# MB_RELAY.net
KiCad netlist of a schematic drawn in Altium Designer
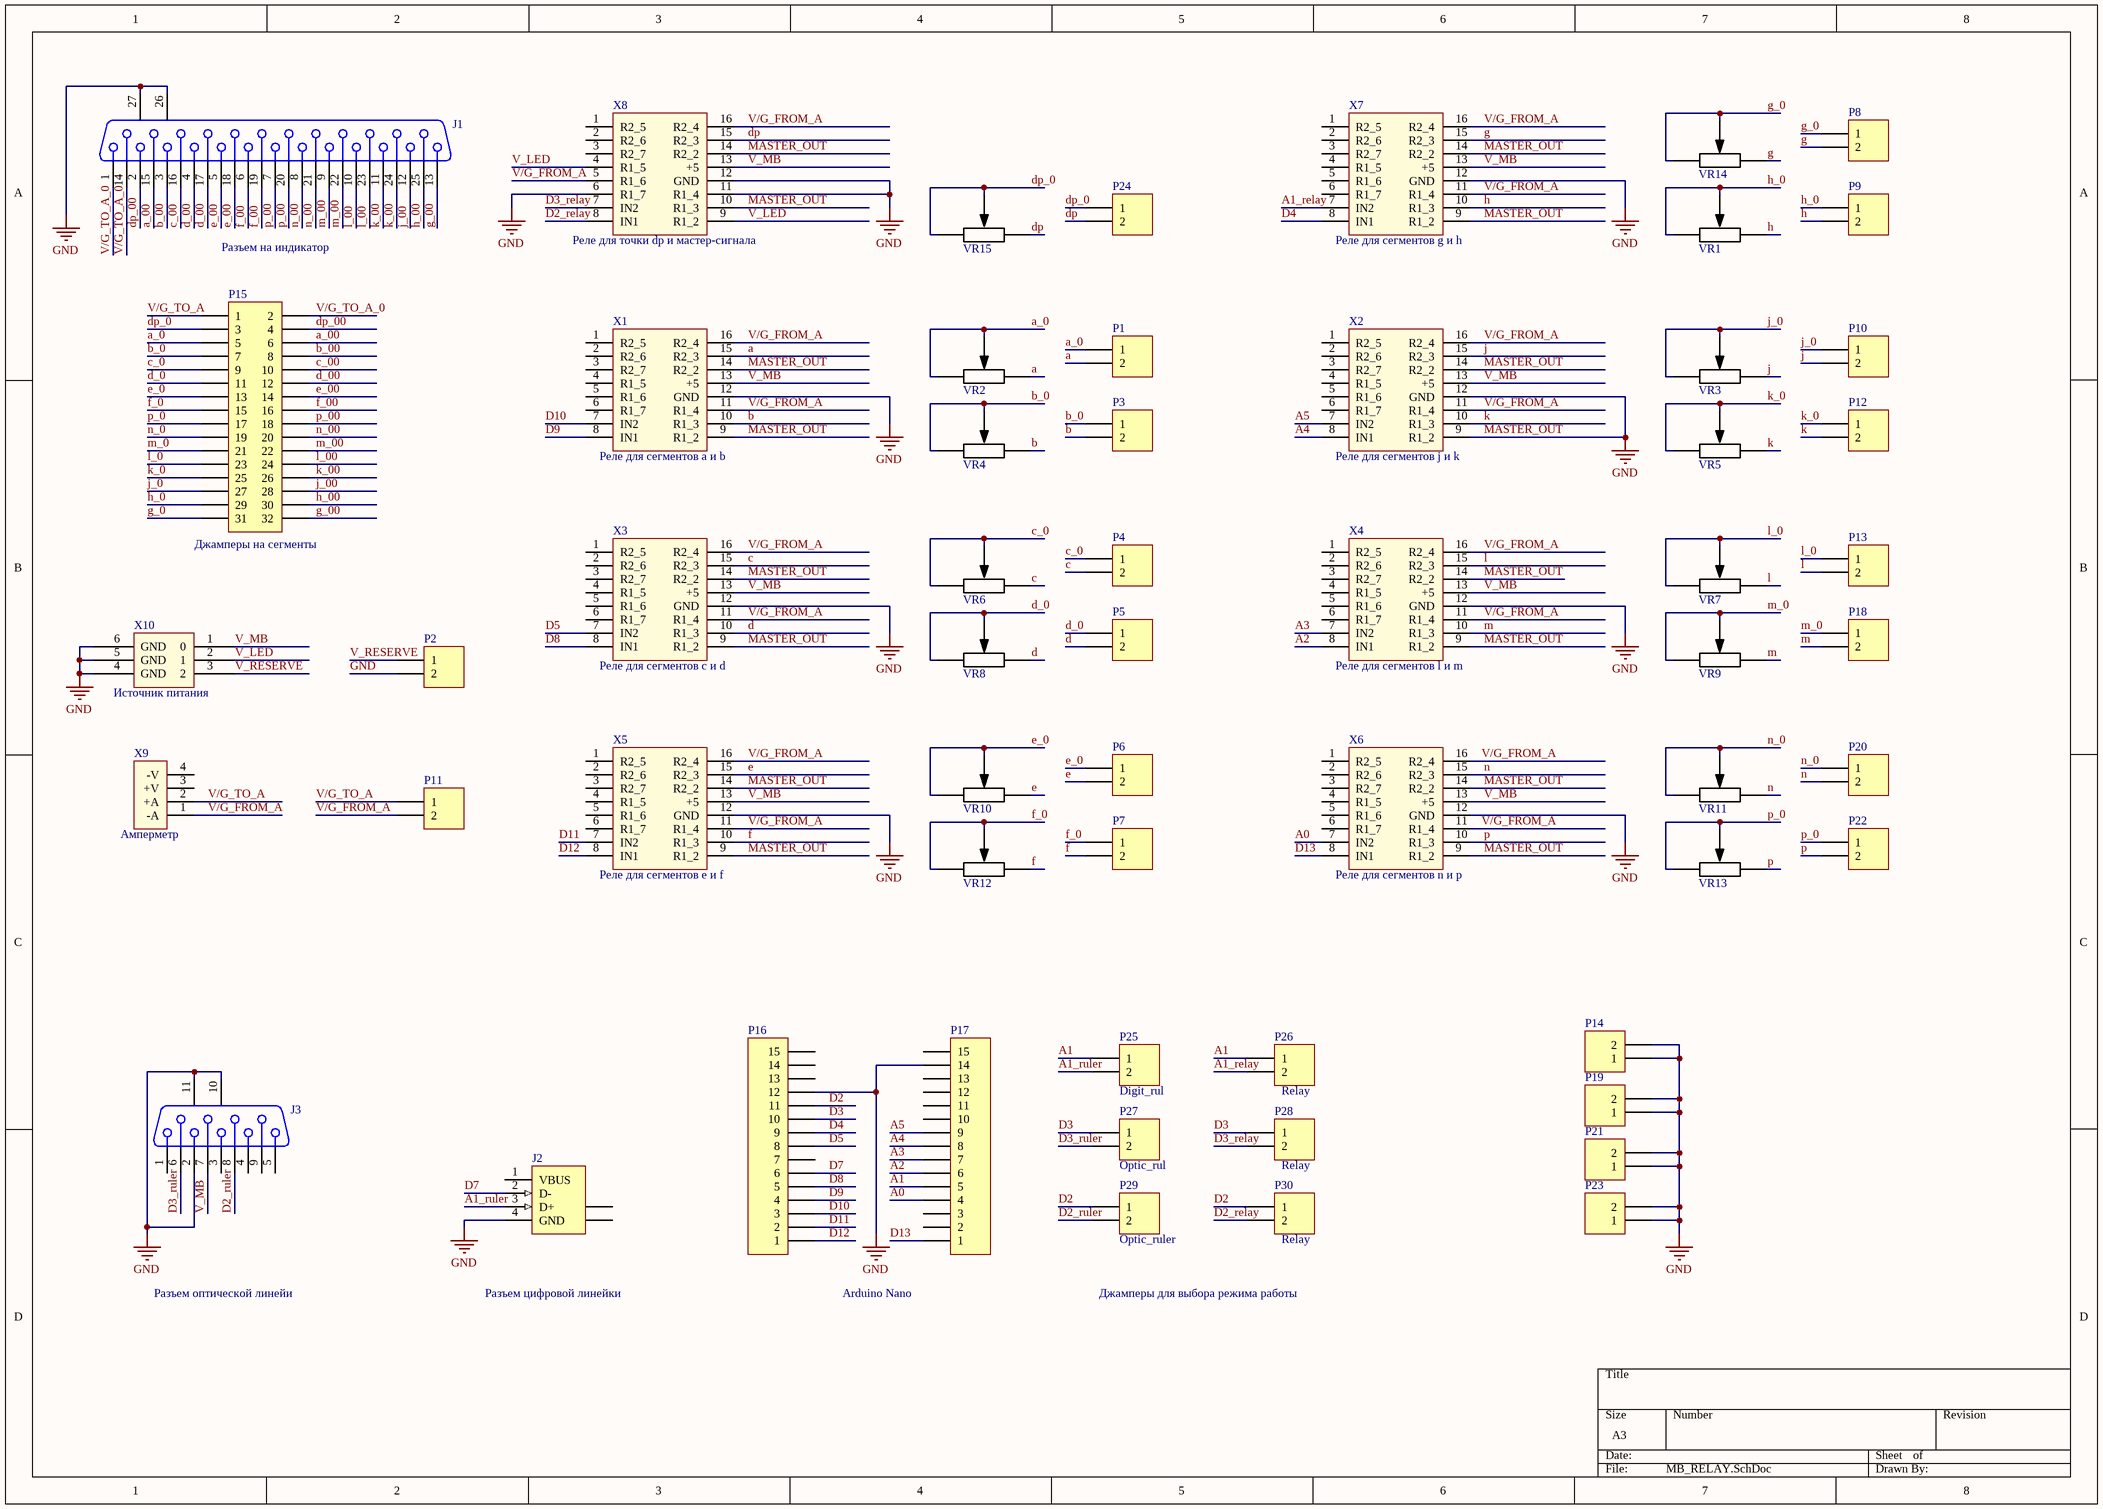
[diagram p0: MB_RELAY.SchDoc]

(export (version "E")
  (design (tool "Eeschema 10.0.6"))
  (components
    (comp (ref "J1")
      (value "D Connector 25")
      (footprint "DSUB1.385-2H25A")
      (description "Receptacle Assembly, 25 Position, Right Angle")
      (fields (field (name "PUBLISHER") "Altium Limited"))
      (libsource (lib "Miscellaneous Connectors") (part "D Connector 25"))
    )
    (comp (ref "J2")
      (value "1-353576-1")
      (footprint "353576")
      (description "USB 1.1, Right Angle, SMT, A Type, Receptacle, 4 Position, White")
      (fields (field (name "PUBLISHER") "Altium Limited"))
      (libsource (lib "AMP Serial Bus USB") (part "1-353576-1"))
    )
    (comp (ref "J3")
      (value "D Connector 9")
      (footprint "DSUB1.385-2H9")
      (description "Receptacle Assembly, 9 Position, Right Angle")
      (fields (field (name "PUBLISHER") "Altium Limited"))
      (libsource (lib "Miscellaneous Connectors") (part "D Connector 9"))
    )
    (comp (ref "P1")
      (value "Header 2")
      (footprint "HDR1X2")
      (description "Header, 2-Pin")
      (fields (field (name "PUBLISHER") "Altium Limited"))
      (libsource (lib "Miscellaneous Connectors") (part "Header 2"))
    )
    (comp (ref "P2")
      (value "Header 2")
      (footprint "HDR1X2")
      (description "Header, 2-Pin")
      (fields (field (name "PUBLISHER") "Altium Limited"))
      (libsource (lib "Miscellaneous Connectors") (part "Header 2"))
    )
    (comp (ref "P3")
      (value "Header 2")
      (footprint "HDR1X2")
      (description "Header, 2-Pin")
      (fields (field (name "PUBLISHER") "Altium Limited"))
      (libsource (lib "Miscellaneous Connectors") (part "Header 2"))
    )
    (comp (ref "P4")
      (value "Header 2")
      (footprint "HDR1X2")
      (description "Header, 2-Pin")
      (fields (field (name "PUBLISHER") "Altium Limited"))
      (libsource (lib "Miscellaneous Connectors") (part "Header 2"))
    )
    (comp (ref "P5")
      (value "Header 2")
      (footprint "HDR1X2")
      (description "Header, 2-Pin")
      (fields (field (name "PUBLISHER") "Altium Limited"))
      (libsource (lib "Miscellaneous Connectors") (part "Header 2"))
    )
    (comp (ref "P6")
      (value "GND")
      (footprint "HDR1X2")
      (description "Header, 2-Pin")
      (fields (field (name "PUBLISHER") "Altium Limited"))
      (libsource (lib "Miscellaneous Connectors") (part "Header 2"))
    )
    (comp (ref "P7")
      (value "GND")
      (footprint "HDR1X2")
      (description "Header, 2-Pin")
      (fields (field (name "PUBLISHER") "Altium Limited"))
      (libsource (lib "Miscellaneous Connectors") (part "Header 2"))
    )
    (comp (ref "P8")
      (value "GND")
      (footprint "HDR1X2")
      (description "Header, 2-Pin")
      (fields (field (name "PUBLISHER") "Altium Limited"))
      (libsource (lib "Miscellaneous Connectors") (part "Header 2"))
    )
    (comp (ref "P9")
      (value "GND")
      (footprint "HDR1X2")
      (description "Header, 2-Pin")
      (fields (field (name "PUBLISHER") "Altium Limited"))
      (libsource (lib "Miscellaneous Connectors") (part "Header 2"))
    )
    (comp (ref "P10")
      (value "Header 2")
      (footprint "HDR1X2")
      (description "Header, 2-Pin")
      (fields (field (name "PUBLISHER") "Altium Limited"))
      (libsource (lib "Miscellaneous Connectors") (part "Header 2"))
    )
    (comp (ref "P11")
      (value "Header 2")
      (footprint "HDR1X2")
      (description "Header, 2-Pin")
      (fields (field (name "PUBLISHER") "Altium Limited"))
      (libsource (lib "Miscellaneous Connectors") (part "Header 2"))
    )
    (comp (ref "P12")
      (value "Header 2")
      (footprint "HDR1X2")
      (description "Header, 2-Pin")
      (fields (field (name "PUBLISHER") "Altium Limited"))
      (libsource (lib "Miscellaneous Connectors") (part "Header 2"))
    )
    (comp (ref "P13")
      (value "GND")
      (footprint "HDR1X2")
      (description "Header, 2-Pin")
      (fields (field (name "PUBLISHER") "Altium Limited"))
      (libsource (lib "Miscellaneous Connectors") (part "Header 2"))
    )
    (comp (ref "P14")
      (value "GND")
      (footprint "HDR1X2")
      (description "Header, 2-Pin")
      (fields (field (name "PUBLISHER") "Altium Limited"))
      (libsource (lib "") (part "Header 2_1"))
    )
    (comp (ref "P15")
      (value "Header 16X2")
      (footprint "HDR2X16")
      (description "Header, 16-Pin, Dual row")
      (fields (field (name "PUBLISHER") "Altium Limited"))
      (libsource (lib "Miscellaneous Connectors") (part "Header 16X2"))
    )
    (comp (ref "P16")
      (value "Header 15")
      (footprint "HDR1X15")
      (description "Header, 15-Pin")
      (fields (field (name "PUBLISHER") "Altium Limited"))
      (libsource (lib "Miscellaneous Connectors") (part "Header 15"))
    )
    (comp (ref "P17")
      (value "Header 15")
      (footprint "HDR1X15")
      (description "Header, 15-Pin")
      (fields (field (name "PUBLISHER") "Altium Limited"))
      (libsource (lib "") (part "Header 15_1"))
    )
    (comp (ref "P18")
      (value "GND")
      (footprint "HDR1X2")
      (description "Header, 2-Pin")
      (fields (field (name "PUBLISHER") "Altium Limited"))
      (libsource (lib "Miscellaneous Connectors") (part "Header 2"))
    )
    (comp (ref "P19")
      (value "GND")
      (footprint "HDR1X2")
      (description "Header, 2-Pin")
      (fields (field (name "PUBLISHER") "Altium Limited"))
      (libsource (lib "") (part "Header 2_1"))
    )
    (comp (ref "P20")
      (value "GND")
      (footprint "HDR1X2")
      (description "Header, 2-Pin")
      (fields (field (name "PUBLISHER") "Altium Limited"))
      (libsource (lib "Miscellaneous Connectors") (part "Header 2"))
    )
    (comp (ref "P21")
      (value "GND")
      (footprint "HDR1X2")
      (description "Header, 2-Pin")
      (fields (field (name "PUBLISHER") "Altium Limited"))
      (libsource (lib "") (part "Header 2_1"))
    )
    (comp (ref "P22")
      (value "GND")
      (footprint "HDR1X2")
      (description "Header, 2-Pin")
      (fields (field (name "PUBLISHER") "Altium Limited"))
      (libsource (lib "Miscellaneous Connectors") (part "Header 2"))
    )
    (comp (ref "P23")
      (value "GND")
      (footprint "HDR1X2")
      (description "Header, 2-Pin")
      (fields (field (name "PUBLISHER") "Altium Limited"))
      (libsource (lib "") (part "Header 2_1"))
    )
    (comp (ref "P24")
      (value "GND")
      (footprint "HDR1X2")
      (description "Header, 2-Pin")
      (fields (field (name "PUBLISHER") "Altium Limited"))
      (libsource (lib "Miscellaneous Connectors") (part "Header 2"))
    )
    (comp (ref "P25")
      (value "Digit_rul")
      (footprint "HDR1X2")
      (description "Header, 2-Pin")
      (fields (field (name "PUBLISHER") "Altium Limited"))
      (libsource (lib "Miscellaneous Connectors") (part "Header 2"))
    )
    (comp (ref "P26")
      (value "Relay")
      (footprint "HDR1X2")
      (description "Header, 2-Pin")
      (fields (field (name "PUBLISHER") "Altium Limited"))
      (libsource (lib "Miscellaneous Connectors") (part "Header 2"))
    )
    (comp (ref "P27")
      (value "Optic_rul")
      (footprint "HDR1X2")
      (description "Header, 2-Pin")
      (fields (field (name "PUBLISHER") "Altium Limited"))
      (libsource (lib "Miscellaneous Connectors") (part "Header 2"))
    )
    (comp (ref "P28")
      (value "Relay")
      (footprint "HDR1X2")
      (description "Header, 2-Pin")
      (fields (field (name "PUBLISHER") "Altium Limited"))
      (libsource (lib "Miscellaneous Connectors") (part "Header 2"))
    )
    (comp (ref "P29")
      (value "Optic_ruler")
      (footprint "HDR1X2")
      (description "Header, 2-Pin")
      (fields (field (name "PUBLISHER") "Altium Limited"))
      (libsource (lib "Miscellaneous Connectors") (part "Header 2"))
    )
    (comp (ref "P30")
      (value "Relay")
      (footprint "HDR1X2")
      (description "Header, 2-Pin")
      (fields (field (name "PUBLISHER") "Altium Limited"))
      (libsource (lib "Miscellaneous Connectors") (part "Header 2"))
    )
    (comp (ref "VR1")
      (value "RES 3266W")
      (footprint "aab_Passive:RES 3266W")
      (libsource (lib "aab_Schlib") (part "RES 3266W"))
    )
    (comp (ref "VR2")
      (value "Переменнный резистор для")
      (footprint "aab_Passive:RES 3266W")
      (libsource (lib "aab_Schlib") (part "RES 3266W"))
    )
    (comp (ref "VR3")
      (value "RES 3266W")
      (footprint "aab_Passive:RES 3266W")
      (libsource (lib "aab_Schlib") (part "RES 3266W"))
    )
    (comp (ref "VR4")
      (value "RES 3266W")
      (footprint "aab_Passive:RES 3266W")
      (libsource (lib "aab_Schlib") (part "RES 3266W"))
    )
    (comp (ref "VR5")
      (value "RES 3266W")
      (footprint "aab_Passive:RES 3266W")
      (libsource (lib "aab_Schlib") (part "RES 3266W"))
    )
    (comp (ref "VR6")
      (value "RES 3266W")
      (footprint "aab_Passive:RES 3266W")
      (libsource (lib "aab_Schlib") (part "RES 3266W"))
    )
    (comp (ref "VR7")
      (value "RES 3266W")
      (footprint "aab_Passive:RES 3266W")
      (libsource (lib "aab_Schlib") (part "RES 3266W"))
    )
    (comp (ref "VR8")
      (value "RES 3266W")
      (footprint "aab_Passive:RES 3266W")
      (libsource (lib "aab_Schlib") (part "RES 3266W"))
    )
    (comp (ref "VR9")
      (value "RES 3266W")
      (footprint "aab_Passive:RES 3266W")
      (libsource (lib "aab_Schlib") (part "RES 3266W"))
    )
    (comp (ref "VR10")
      (value "RES 3266W")
      (footprint "aab_Passive:RES 3266W")
      (libsource (lib "aab_Schlib") (part "RES 3266W"))
    )
    (comp (ref "VR11")
      (value "RES 3266W")
      (footprint "aab_Passive:RES 3266W")
      (libsource (lib "aab_Schlib") (part "RES 3266W"))
    )
    (comp (ref "VR12")
      (value "RES 3266W")
      (footprint "aab_Passive:RES 3266W")
      (libsource (lib "aab_Schlib") (part "RES 3266W"))
    )
    (comp (ref "VR13")
      (value "RES 3266W")
      (footprint "aab_Passive:RES 3266W")
      (libsource (lib "aab_Schlib") (part "RES 3266W"))
    )
    (comp (ref "VR14")
      (value "RES 3266W")
      (footprint "aab_Passive:RES 3266W")
      (libsource (lib "aab_Schlib") (part "RES 3266W"))
    )
    (comp (ref "VR15")
      (value "RES 3266W")
      (footprint "aab_Passive:RES 3266W")
      (libsource (lib "aab_Schlib") (part "RES 3266W"))
    )
    (comp (ref "X1")
      (value "Реле для сегментов a и b")
      (footprint "MEZ_RELAY")
      (libsource (lib "msp_SchLib") (part "MEZ_RELAY"))
    )
    (comp (ref "X2")
      (value "Реле для сегментов j и k")
      (footprint "MEZ_RELAY")
      (libsource (lib "msp_SchLib") (part "MEZ_RELAY"))
    )
    (comp (ref "X3")
      (value "Реле для сегментов c и d")
      (footprint "MEZ_RELAY")
      (libsource (lib "msp_SchLib") (part "MEZ_RELAY"))
    )
    (comp (ref "X4")
      (value "Реле для сегментов l и m")
      (footprint "MEZ_RELAY")
      (libsource (lib "msp_SchLib") (part "MEZ_RELAY"))
    )
    (comp (ref "X5")
      (value "Реле для сегментов e и f")
      (footprint "MEZ_RELAY")
      (libsource (lib "msp_SchLib") (part "MEZ_RELAY"))
    )
    (comp (ref "X6")
      (value "Реле для сегментов n и p")
      (footprint "MEZ_RELAY")
      (libsource (lib "msp_SchLib") (part "MEZ_RELAY"))
    )
    (comp (ref "X7")
      (value "Реле для сегментов g и h")
      (footprint "MEZ_RELAY")
      (libsource (lib "msp_SchLib") (part "MEZ_RELAY"))
    )
    (comp (ref "X8")
      (value "Реле для точки dp и мастер-сигнала")
      (footprint "MEZ_RELAY")
      (libsource (lib "msp_SchLib") (part "MEZ_RELAY"))
    )
    (comp (ref "X9")
      (value "Амперметр")
      (footprint "vpl_Passive:AMP_VOLTMETER")
      (libsource (lib "msp_SchLib") (part "AMP_VOLTMETR"))
    )
    (comp (ref "X10")
      (value "Источник питания")
      (footprint "vpl_Passive:POWER")
      (libsource (lib "msp_SchLib") (part "POWER"))
    )
  )
  (nets
    (net (code "1") (name "/A0") (class "Default")
      (node (ref "P17") (pin "4") (pinfunction "4_4") (pintype "passive"))
      (node (ref "X6") (pin "7") (pinfunction "IN2_7") (pintype "passive"))
    )
    (net (code "2") (name "/A1") (class "Default")
      (node (ref "P17") (pin "5") (pinfunction "5_5") (pintype "passive"))
      (node (ref "P25") (pin "1") (pinfunction "1_1") (pintype "passive"))
      (node (ref "P26") (pin "1") (pinfunction "1_1") (pintype "passive"))
    )
    (net (code "3") (name "/A1_relay") (class "Default")
      (node (ref "P26") (pin "2") (pinfunction "2_2") (pintype "passive"))
      (node (ref "X7") (pin "7") (pinfunction "IN2_7") (pintype "passive"))
    )
    (net (code "4") (name "/A1_ruler") (class "Default")
      (node (ref "J2") (pin "3") (pinfunction "D+_3") (pintype "input"))
      (node (ref "P25") (pin "2") (pinfunction "2_2") (pintype "passive"))
    )
    (net (code "5") (name "/A2") (class "Default")
      (node (ref "P17") (pin "6") (pinfunction "6_6") (pintype "passive"))
      (node (ref "X4") (pin "8") (pinfunction "IN1_8") (pintype "passive"))
    )
    (net (code "6") (name "/A3") (class "Default")
      (node (ref "P17") (pin "7") (pinfunction "7_7") (pintype "passive"))
      (node (ref "X4") (pin "7") (pinfunction "IN2_7") (pintype "passive"))
    )
    (net (code "7") (name "/A4") (class "Default")
      (node (ref "P17") (pin "8") (pinfunction "8_8") (pintype "passive"))
      (node (ref "X2") (pin "8") (pinfunction "IN1_8") (pintype "passive"))
    )
    (net (code "8") (name "/A5") (class "Default")
      (node (ref "P17") (pin "9") (pinfunction "9_9") (pintype "passive"))
      (node (ref "X2") (pin "7") (pinfunction "IN2_7") (pintype "passive"))
    )
    (net (code "9") (name "/D2") (class "Default")
      (node (ref "P16") (pin "11") (pinfunction "11_11") (pintype "passive"))
      (node (ref "P29") (pin "1") (pinfunction "1_1") (pintype "passive"))
      (node (ref "P30") (pin "1") (pinfunction "1_1") (pintype "passive"))
    )
    (net (code "10") (name "/D2_relay") (class "Default")
      (node (ref "P30") (pin "2") (pinfunction "2_2") (pintype "passive"))
      (node (ref "X8") (pin "8") (pinfunction "IN1_8") (pintype "passive"))
    )
    (net (code "11") (name "/D2_ruler") (class "Default")
      (node (ref "J3") (pin "8") (pinfunction "8_8") (pintype "passive"))
      (node (ref "P29") (pin "2") (pinfunction "2_2") (pintype "passive"))
    )
    (net (code "12") (name "/D3") (class "Default")
      (node (ref "P16") (pin "10") (pinfunction "10_10") (pintype "passive"))
      (node (ref "P27") (pin "1") (pinfunction "1_1") (pintype "passive"))
      (node (ref "P28") (pin "1") (pinfunction "1_1") (pintype "passive"))
    )
    (net (code "13") (name "/D3_relay") (class "Default")
      (node (ref "P28") (pin "2") (pinfunction "2_2") (pintype "passive"))
      (node (ref "X8") (pin "7") (pinfunction "IN2_7") (pintype "passive"))
    )
    (net (code "14") (name "/D3_ruler") (class "Default")
      (node (ref "J3") (pin "6") (pinfunction "6_6") (pintype "passive"))
      (node (ref "P27") (pin "2") (pinfunction "2_2") (pintype "passive"))
    )
    (net (code "15") (name "/D4") (class "Default")
      (node (ref "P16") (pin "9") (pinfunction "9_9") (pintype "passive"))
      (node (ref "X7") (pin "8") (pinfunction "IN1_8") (pintype "passive"))
    )
    (net (code "16") (name "/D5") (class "Default")
      (node (ref "P16") (pin "8") (pinfunction "8_8") (pintype "passive"))
      (node (ref "X3") (pin "7") (pinfunction "IN2_7") (pintype "passive"))
    )
    (net (code "17") (name "/D7") (class "Default")
      (node (ref "J2") (pin "2") (pinfunction "D-_2") (pintype "input"))
      (node (ref "P16") (pin "6") (pinfunction "6_6") (pintype "passive"))
    )
    (net (code "18") (name "/D8") (class "Default")
      (node (ref "P16") (pin "5") (pinfunction "5_5") (pintype "passive"))
      (node (ref "X3") (pin "8") (pinfunction "IN1_8") (pintype "passive"))
    )
    (net (code "19") (name "/D9") (class "Default")
      (node (ref "P16") (pin "4") (pinfunction "4_4") (pintype "passive"))
      (node (ref "X1") (pin "8") (pinfunction "IN1_8") (pintype "passive"))
    )
    (net (code "20") (name "/D10") (class "Default")
      (node (ref "P16") (pin "3") (pinfunction "3_3") (pintype "passive"))
      (node (ref "X1") (pin "7") (pinfunction "IN2_7") (pintype "passive"))
    )
    (net (code "21") (name "/D11") (class "Default")
      (node (ref "P16") (pin "2") (pinfunction "2_2") (pintype "passive"))
      (node (ref "X5") (pin "7") (pinfunction "IN2_7") (pintype "passive"))
    )
    (net (code "22") (name "/D12") (class "Default")
      (node (ref "P16") (pin "1") (pinfunction "1_1") (pintype "passive"))
      (node (ref "X5") (pin "8") (pinfunction "IN1_8") (pintype "passive"))
    )
    (net (code "23") (name "/D13") (class "Default")
      (node (ref "P17") (pin "1") (pinfunction "1_1") (pintype "passive"))
      (node (ref "X6") (pin "8") (pinfunction "IN1_8") (pintype "passive"))
    )
    (net (code "24") (name "/V_LED") (class "Default")
      (node (ref "X10") (pin "2") (pinfunction "1_2") (pintype "passive"))
      (node (ref "X8") (pin "4") (pinfunction "R1_5_4") (pintype "passive"))
      (node (ref "X8") (pin "9") (pinfunction "R1_2_9") (pintype "passive"))
    )
    (net (code "25") (name "/V_MB") (class "Default")
      (node (ref "J3") (pin "7") (pinfunction "7_7") (pintype "passive"))
      (node (ref "X1") (pin "13") (pinfunction "+5_13") (pintype "passive"))
      (node (ref "X10") (pin "1") (pinfunction "0_1") (pintype "passive"))
      (node (ref "X2") (pin "13") (pinfunction "+5_13") (pintype "passive"))
      (node (ref "X3") (pin "13") (pinfunction "+5_13") (pintype "passive"))
      (node (ref "X4") (pin "13") (pinfunction "+5_13") (pintype "passive"))
      (node (ref "X5") (pin "13") (pinfunction "+5_13") (pintype "passive"))
      (node (ref "X6") (pin "13") (pinfunction "+5_13") (pintype "passive"))
      (node (ref "X7") (pin "13") (pinfunction "+5_13") (pintype "passive"))
      (node (ref "X8") (pin "13") (pinfunction "+5_13") (pintype "passive"))
    )
    (net (code "26") (name "/V_RESERVE") (class "Default")
      (node (ref "P2") (pin "1") (pinfunction "1_1") (pintype "passive"))
      (node (ref "X10") (pin "3") (pinfunction "2_3") (pintype "passive"))
    )
    (net (code "27") (name "/V{slash}G_FROM_A") (class "Default")
      (node (ref "P11") (pin "2") (pinfunction "2_2") (pintype "passive"))
      (node (ref "X1") (pin "11") (pinfunction "R1_4_11") (pintype "passive"))
      (node (ref "X1") (pin "16") (pinfunction "R2_4_16") (pintype "passive"))
      (node (ref "X2") (pin "11") (pinfunction "R1_4_11") (pintype "passive"))
      (node (ref "X2") (pin "16") (pinfunction "R2_4_16") (pintype "passive"))
      (node (ref "X3") (pin "11") (pinfunction "R1_4_11") (pintype "passive"))
      (node (ref "X3") (pin "16") (pinfunction "R2_4_16") (pintype "passive"))
      (node (ref "X4") (pin "11") (pinfunction "R1_4_11") (pintype "passive"))
      (node (ref "X4") (pin "16") (pinfunction "R2_4_16") (pintype "passive"))
      (node (ref "X5") (pin "11") (pinfunction "R1_4_11") (pintype "passive"))
      (node (ref "X5") (pin "16") (pinfunction "R2_4_16") (pintype "passive"))
      (node (ref "X6") (pin "11") (pinfunction "R1_4_11") (pintype "passive"))
      (node (ref "X6") (pin "16") (pinfunction "R2_4_16") (pintype "passive"))
      (node (ref "X7") (pin "11") (pinfunction "R1_4_11") (pintype "passive"))
      (node (ref "X7") (pin "16") (pinfunction "R2_4_16") (pintype "passive"))
      (node (ref "X8") (pin "16") (pinfunction "R2_4_16") (pintype "passive"))
      (node (ref "X8") (pin "5") (pinfunction "R1_6_5") (pintype "passive"))
      (node (ref "X9") (pin "1") (pinfunction "-A_1") (pintype "passive"))
    )
    (net (code "28") (name "/V{slash}G_TO_A") (class "Default")
      (node (ref "P11") (pin "1") (pinfunction "1_1") (pintype "passive"))
      (node (ref "P15") (pin "1") (pinfunction "1_1") (pintype "passive"))
      (node (ref "X9") (pin "2") (pinfunction "+A_2") (pintype "passive"))
    )
    (net (code "29") (name "/V{slash}G_TO_A_0") (class "Default")
      (node (ref "J1") (pin "1") (pinfunction "1_1") (pintype "passive"))
      (node (ref "J1") (pin "14") (pinfunction "14_14") (pintype "passive"))
      (node (ref "P15") (pin "2") (pinfunction "2_2") (pintype "passive"))
    )
    (net (code "30") (name "/a") (class "Default")
      (node (ref "P1") (pin "2") (pinfunction "2_2") (pintype "passive"))
      (node (ref "VR2") (pin "3") (pinfunction "3_3") (pintype "passive"))
      (node (ref "X1") (pin "15") (pinfunction "R2_3_15") (pintype "passive"))
    )
    (net (code "31") (name "/a_0") (class "Default")
      (node (ref "P1") (pin "1") (pinfunction "1_1") (pintype "passive"))
      (node (ref "P15") (pin "5") (pinfunction "5_5") (pintype "passive"))
      (node (ref "VR2") (pin "1") (pinfunction "1_1") (pintype "passive"))
      (node (ref "VR2") (pin "2") (pinfunction "2_2") (pintype "passive"))
    )
    (net (code "32") (name "/a_00") (class "Default")
      (node (ref "J1") (pin "15") (pinfunction "15_15") (pintype "passive"))
      (node (ref "P15") (pin "6") (pinfunction "6_6") (pintype "passive"))
    )
    (net (code "33") (name "/b") (class "Default")
      (node (ref "P3") (pin "2") (pinfunction "2_2") (pintype "passive"))
      (node (ref "VR4") (pin "3") (pinfunction "3_3") (pintype "passive"))
      (node (ref "X1") (pin "10") (pinfunction "R1_3_10") (pintype "passive"))
    )
    (net (code "34") (name "/b_00") (class "Default")
      (node (ref "J1") (pin "3") (pinfunction "3_3") (pintype "passive"))
      (node (ref "P15") (pin "8") (pinfunction "8_8") (pintype "passive"))
    )
    (net (code "35") (name "/b_0") (class "Default")
      (node (ref "P15") (pin "7") (pinfunction "7_7") (pintype "passive"))
      (node (ref "P3") (pin "1") (pinfunction "1_1") (pintype "passive"))
      (node (ref "VR4") (pin "1") (pinfunction "1_1") (pintype "passive"))
      (node (ref "VR4") (pin "2") (pinfunction "2_2") (pintype "passive"))
    )
    (net (code "36") (name "/c") (class "Default")
      (node (ref "P4") (pin "2") (pinfunction "2_2") (pintype "passive"))
      (node (ref "VR6") (pin "3") (pinfunction "3_3") (pintype "passive"))
      (node (ref "X3") (pin "15") (pinfunction "R2_3_15") (pintype "passive"))
    )
    (net (code "37") (name "/c_0") (class "Default")
      (node (ref "P15") (pin "9") (pinfunction "9_9") (pintype "passive"))
      (node (ref "P4") (pin "1") (pinfunction "1_1") (pintype "passive"))
      (node (ref "VR6") (pin "1") (pinfunction "1_1") (pintype "passive"))
      (node (ref "VR6") (pin "2") (pinfunction "2_2") (pintype "passive"))
    )
    (net (code "38") (name "/c_00") (class "Default")
      (node (ref "J1") (pin "16") (pinfunction "16_16") (pintype "passive"))
      (node (ref "P15") (pin "10") (pinfunction "10_10") (pintype "passive"))
    )
    (net (code "39") (name "/d") (class "Default")
      (node (ref "P5") (pin "2") (pinfunction "2_2") (pintype "passive"))
      (node (ref "VR8") (pin "3") (pinfunction "3_3") (pintype "passive"))
      (node (ref "X3") (pin "10") (pinfunction "R1_3_10") (pintype "passive"))
    )
    (net (code "40") (name "/d_0") (class "Default")
      (node (ref "P15") (pin "11") (pinfunction "11_11") (pintype "passive"))
      (node (ref "P5") (pin "1") (pinfunction "1_1") (pintype "passive"))
      (node (ref "VR8") (pin "1") (pinfunction "1_1") (pintype "passive"))
      (node (ref "VR8") (pin "2") (pinfunction "2_2") (pintype "passive"))
    )
    (net (code "41") (name "/d_00") (class "Default")
      (node (ref "J1") (pin "17") (pinfunction "17_17") (pintype "passive"))
      (node (ref "J1") (pin "4") (pinfunction "4_4") (pintype "passive"))
      (node (ref "P15") (pin "12") (pinfunction "12_12") (pintype "passive"))
    )
    (net (code "42") (name "/dp") (class "Default")
      (node (ref "P24") (pin "2") (pinfunction "2_2") (pintype "passive"))
      (node (ref "VR15") (pin "3") (pinfunction "3_3") (pintype "passive"))
      (node (ref "X8") (pin "15") (pinfunction "R2_3_15") (pintype "passive"))
    )
    (net (code "43") (name "/dp_0") (class "Default")
      (node (ref "P15") (pin "3") (pinfunction "3_3") (pintype "passive"))
      (node (ref "P24") (pin "1") (pinfunction "1_1") (pintype "passive"))
      (node (ref "VR15") (pin "1") (pinfunction "1_1") (pintype "passive"))
      (node (ref "VR15") (pin "2") (pinfunction "2_2") (pintype "passive"))
    )
    (net (code "44") (name "/dp_00") (class "Default")
      (node (ref "J1") (pin "2") (pinfunction "2_2") (pintype "passive"))
      (node (ref "P15") (pin "4") (pinfunction "4_4") (pintype "passive"))
    )
    (net (code "45") (name "/e") (class "Default")
      (node (ref "P6") (pin "2") (pinfunction "2_2") (pintype "passive"))
      (node (ref "VR10") (pin "3") (pinfunction "3_3") (pintype "passive"))
      (node (ref "X5") (pin "15") (pinfunction "R2_3_15") (pintype "passive"))
    )
    (net (code "46") (name "/e_0") (class "Default")
      (node (ref "P15") (pin "13") (pinfunction "13_13") (pintype "passive"))
      (node (ref "P6") (pin "1") (pinfunction "1_1") (pintype "passive"))
      (node (ref "VR10") (pin "1") (pinfunction "1_1") (pintype "passive"))
      (node (ref "VR10") (pin "2") (pinfunction "2_2") (pintype "passive"))
    )
    (net (code "47") (name "/e_00") (class "Default")
      (node (ref "J1") (pin "18") (pinfunction "18_18") (pintype "passive"))
      (node (ref "J1") (pin "5") (pinfunction "5_5") (pintype "passive"))
      (node (ref "P15") (pin "14") (pinfunction "14_14") (pintype "passive"))
    )
    (net (code "48") (name "/f") (class "Default")
      (node (ref "P7") (pin "2") (pinfunction "2_2") (pintype "passive"))
      (node (ref "VR12") (pin "3") (pinfunction "3_3") (pintype "passive"))
      (node (ref "X5") (pin "10") (pinfunction "R1_3_10") (pintype "passive"))
    )
    (net (code "49") (name "/f_0") (class "Default")
      (node (ref "P15") (pin "15") (pinfunction "15_15") (pintype "passive"))
      (node (ref "P7") (pin "1") (pinfunction "1_1") (pintype "passive"))
      (node (ref "VR12") (pin "1") (pinfunction "1_1") (pintype "passive"))
      (node (ref "VR12") (pin "2") (pinfunction "2_2") (pintype "passive"))
    )
    (net (code "50") (name "/f_00") (class "Default")
      (node (ref "J1") (pin "19") (pinfunction "19_19") (pintype "passive"))
      (node (ref "J1") (pin "6") (pinfunction "6_6") (pintype "passive"))
      (node (ref "P15") (pin "16") (pinfunction "16_16") (pintype "passive"))
    )
    (net (code "51") (name "/g") (class "Default")
      (node (ref "P8") (pin "2") (pinfunction "2_2") (pintype "passive"))
      (node (ref "VR14") (pin "3") (pinfunction "3_3") (pintype "passive"))
      (node (ref "X7") (pin "15") (pinfunction "R2_3_15") (pintype "passive"))
    )
    (net (code "52") (name "/g_00") (class "Default")
      (node (ref "J1") (pin "13") (pinfunction "13_13") (pintype "passive"))
      (node (ref "P15") (pin "32") (pinfunction "32_32") (pintype "passive"))
    )
    (net (code "53") (name "/g_0") (class "Default")
      (node (ref "P15") (pin "31") (pinfunction "31_31") (pintype "passive"))
      (node (ref "P8") (pin "1") (pinfunction "1_1") (pintype "passive"))
      (node (ref "VR14") (pin "1") (pinfunction "1_1") (pintype "passive"))
      (node (ref "VR14") (pin "2") (pinfunction "2_2") (pintype "passive"))
    )
    (net (code "54") (name "/h") (class "Default")
      (node (ref "P9") (pin "2") (pinfunction "2_2") (pintype "passive"))
      (node (ref "VR1") (pin "3") (pinfunction "3_3") (pintype "passive"))
      (node (ref "X7") (pin "10") (pinfunction "R1_3_10") (pintype "passive"))
    )
    (net (code "55") (name "/h_00") (class "Default")
      (node (ref "J1") (pin "25") (pinfunction "25_25") (pintype "passive"))
      (node (ref "P15") (pin "30") (pinfunction "30_30") (pintype "passive"))
    )
    (net (code "56") (name "/h_0") (class "Default")
      (node (ref "P15") (pin "29") (pinfunction "29_29") (pintype "passive"))
      (node (ref "P9") (pin "1") (pinfunction "1_1") (pintype "passive"))
      (node (ref "VR1") (pin "1") (pinfunction "1_1") (pintype "passive"))
      (node (ref "VR1") (pin "2") (pinfunction "2_2") (pintype "passive"))
    )
    (net (code "57") (name "/j") (class "Default")
      (node (ref "P10") (pin "2") (pinfunction "2_2") (pintype "passive"))
      (node (ref "VR3") (pin "3") (pinfunction "3_3") (pintype "passive"))
      (node (ref "X2") (pin "15") (pinfunction "R2_3_15") (pintype "passive"))
    )
    (net (code "58") (name "/j_00") (class "Default")
      (node (ref "J1") (pin "12") (pinfunction "12_12") (pintype "passive"))
      (node (ref "P15") (pin "28") (pinfunction "28_28") (pintype "passive"))
    )
    (net (code "59") (name "/j_0") (class "Default")
      (node (ref "P10") (pin "1") (pinfunction "1_1") (pintype "passive"))
      (node (ref "P15") (pin "27") (pinfunction "27_27") (pintype "passive"))
      (node (ref "VR3") (pin "1") (pinfunction "1_1") (pintype "passive"))
      (node (ref "VR3") (pin "2") (pinfunction "2_2") (pintype "passive"))
    )
    (net (code "60") (name "/k") (class "Default")
      (node (ref "P12") (pin "2") (pinfunction "2_2") (pintype "passive"))
      (node (ref "VR5") (pin "3") (pinfunction "3_3") (pintype "passive"))
      (node (ref "X2") (pin "10") (pinfunction "R1_3_10") (pintype "passive"))
    )
    (net (code "61") (name "/k_0") (class "Default")
      (node (ref "P12") (pin "1") (pinfunction "1_1") (pintype "passive"))
      (node (ref "P15") (pin "25") (pinfunction "25_25") (pintype "passive"))
      (node (ref "VR5") (pin "1") (pinfunction "1_1") (pintype "passive"))
      (node (ref "VR5") (pin "2") (pinfunction "2_2") (pintype "passive"))
    )
    (net (code "62") (name "/k_00") (class "Default")
      (node (ref "J1") (pin "11") (pinfunction "11_11") (pintype "passive"))
      (node (ref "J1") (pin "24") (pinfunction "24_24") (pintype "passive"))
      (node (ref "P15") (pin "26") (pinfunction "26_26") (pintype "passive"))
    )
    (net (code "63") (name "/l") (class "Default")
      (node (ref "P13") (pin "2") (pinfunction "2_2") (pintype "passive"))
      (node (ref "VR7") (pin "3") (pinfunction "3_3") (pintype "passive"))
      (node (ref "X4") (pin "15") (pinfunction "R2_3_15") (pintype "passive"))
    )
    (net (code "64") (name "/l_00") (class "Default")
      (node (ref "J1") (pin "10") (pinfunction "10_10") (pintype "passive"))
      (node (ref "J1") (pin "23") (pinfunction "23_23") (pintype "passive"))
      (node (ref "P15") (pin "24") (pinfunction "24_24") (pintype "passive"))
    )
    (net (code "65") (name "/l_0") (class "Default")
      (node (ref "P13") (pin "1") (pinfunction "1_1") (pintype "passive"))
      (node (ref "P15") (pin "23") (pinfunction "23_23") (pintype "passive"))
      (node (ref "VR7") (pin "1") (pinfunction "1_1") (pintype "passive"))
      (node (ref "VR7") (pin "2") (pinfunction "2_2") (pintype "passive"))
    )
    (net (code "66") (name "/m") (class "Default")
      (node (ref "P18") (pin "2") (pinfunction "2_2") (pintype "passive"))
      (node (ref "VR9") (pin "3") (pinfunction "3_3") (pintype "passive"))
      (node (ref "X4") (pin "10") (pinfunction "R1_3_10") (pintype "passive"))
    )
    (net (code "67") (name "/m_00") (class "Default")
      (node (ref "J1") (pin "22") (pinfunction "22_22") (pintype "passive"))
      (node (ref "J1") (pin "9") (pinfunction "9_9") (pintype "passive"))
      (node (ref "P15") (pin "22") (pinfunction "22_22") (pintype "passive"))
    )
    (net (code "68") (name "/m_0") (class "Default")
      (node (ref "P15") (pin "21") (pinfunction "21_21") (pintype "passive"))
      (node (ref "P18") (pin "1") (pinfunction "1_1") (pintype "passive"))
      (node (ref "VR9") (pin "1") (pinfunction "1_1") (pintype "passive"))
      (node (ref "VR9") (pin "2") (pinfunction "2_2") (pintype "passive"))
    )
    (net (code "69") (name "/n") (class "Default")
      (node (ref "P20") (pin "2") (pinfunction "2_2") (pintype "passive"))
      (node (ref "VR11") (pin "3") (pinfunction "3_3") (pintype "passive"))
      (node (ref "X6") (pin "15") (pinfunction "R2_3_15") (pintype "passive"))
    )
    (net (code "70") (name "/n_0") (class "Default")
      (node (ref "P15") (pin "19") (pinfunction "19_19") (pintype "passive"))
      (node (ref "P20") (pin "1") (pinfunction "1_1") (pintype "passive"))
      (node (ref "VR11") (pin "1") (pinfunction "1_1") (pintype "passive"))
      (node (ref "VR11") (pin "2") (pinfunction "2_2") (pintype "passive"))
    )
    (net (code "71") (name "/n_00") (class "Default")
      (node (ref "J1") (pin "21") (pinfunction "21_21") (pintype "passive"))
      (node (ref "J1") (pin "8") (pinfunction "8_8") (pintype "passive"))
      (node (ref "P15") (pin "20") (pinfunction "20_20") (pintype "passive"))
    )
    (net (code "72") (name "/p") (class "Default")
      (node (ref "P22") (pin "2") (pinfunction "2_2") (pintype "passive"))
      (node (ref "VR13") (pin "3") (pinfunction "3_3") (pintype "passive"))
      (node (ref "X6") (pin "10") (pinfunction "R1_3_10") (pintype "passive"))
    )
    (net (code "73") (name "/p_00") (class "Default")
      (node (ref "J1") (pin "20") (pinfunction "20_20") (pintype "passive"))
      (node (ref "J1") (pin "7") (pinfunction "7_7") (pintype "passive"))
      (node (ref "P15") (pin "18") (pinfunction "18_18") (pintype "passive"))
    )
    (net (code "74") (name "/p_0") (class "Default")
      (node (ref "P15") (pin "17") (pinfunction "17_17") (pintype "passive"))
      (node (ref "P22") (pin "1") (pinfunction "1_1") (pintype "passive"))
      (node (ref "VR13") (pin "1") (pinfunction "1_1") (pintype "passive"))
      (node (ref "VR13") (pin "2") (pinfunction "2_2") (pintype "passive"))
    )
    (net (code "75") (name "GND") (class "Default")
      (node (ref "J1") (pin "26") (pinfunction "MH1_26") (pintype "passive"))
      (node (ref "J1") (pin "27") (pinfunction "MH2_27") (pintype "passive"))
      (node (ref "J2") (pin "4") (pinfunction "GND_4") (pintype "power_in"))
      (node (ref "J3") (pin "10") (pinfunction "MH1_10") (pintype "passive"))
      (node (ref "J3") (pin "11") (pinfunction "MH2_11") (pintype "passive"))
      (node (ref "J3") (pin "2") (pinfunction "2_2") (pintype "passive"))
      (node (ref "P14") (pin "1") (pinfunction "1_1") (pintype "passive"))
      (node (ref "P14") (pin "2") (pinfunction "2_2") (pintype "passive"))
      (node (ref "P16") (pin "12") (pinfunction "12_12") (pintype "passive"))
      (node (ref "P17") (pin "14") (pinfunction "14_14") (pintype "passive"))
      (node (ref "P19") (pin "1") (pinfunction "1_1") (pintype "passive"))
      (node (ref "P19") (pin "2") (pinfunction "2_2") (pintype "passive"))
      (node (ref "P2") (pin "2") (pinfunction "2_2") (pintype "passive"))
      (node (ref "P21") (pin "1") (pinfunction "1_1") (pintype "passive"))
      (node (ref "P21") (pin "2") (pinfunction "2_2") (pintype "passive"))
      (node (ref "P23") (pin "1") (pinfunction "1_1") (pintype "passive"))
      (node (ref "P23") (pin "2") (pinfunction "2_2") (pintype "passive"))
      (node (ref "X1") (pin "12") (pinfunction "GND_12") (pintype "passive"))
      (node (ref "X1") (pin "14") (pinfunction "R2_2_14") (pintype "passive"))
      (node (ref "X1") (pin "9") (pinfunction "R1_2_9") (pintype "passive"))
      (node (ref "X10") (pin "4") (pinfunction "GND_4") (pintype "passive"))
      (node (ref "X10") (pin "5") (pinfunction "GND_5") (pintype "passive"))
      (node (ref "X10") (pin "6") (pinfunction "GND_6") (pintype "passive"))
      (node (ref "X2") (pin "12") (pinfunction "GND_12") (pintype "passive"))
      (node (ref "X2") (pin "14") (pinfunction "R2_2_14") (pintype "passive"))
      (node (ref "X2") (pin "9") (pinfunction "R1_2_9") (pintype "passive"))
      (node (ref "X3") (pin "12") (pinfunction "GND_12") (pintype "passive"))
      (node (ref "X3") (pin "14") (pinfunction "R2_2_14") (pintype "passive"))
      (node (ref "X3") (pin "9") (pinfunction "R1_2_9") (pintype "passive"))
      (node (ref "X4") (pin "12") (pinfunction "GND_12") (pintype "passive"))
      (node (ref "X4") (pin "14") (pinfunction "R2_2_14") (pintype "passive"))
      (node (ref "X4") (pin "9") (pinfunction "R1_2_9") (pintype "passive"))
      (node (ref "X5") (pin "12") (pinfunction "GND_12") (pintype "passive"))
      (node (ref "X5") (pin "14") (pinfunction "R2_2_14") (pintype "passive"))
      (node (ref "X5") (pin "9") (pinfunction "R1_2_9") (pintype "passive"))
      (node (ref "X6") (pin "12") (pinfunction "GND_12") (pintype "passive"))
      (node (ref "X6") (pin "14") (pinfunction "R2_2_14") (pintype "passive"))
      (node (ref "X6") (pin "9") (pinfunction "R1_2_9") (pintype "passive"))
      (node (ref "X7") (pin "12") (pinfunction "GND_12") (pintype "passive"))
      (node (ref "X7") (pin "14") (pinfunction "R2_2_14") (pintype "passive"))
      (node (ref "X7") (pin "9") (pinfunction "R1_2_9") (pintype "passive"))
      (node (ref "X8") (pin "10") (pinfunction "R1_3_10") (pintype "passive"))
      (node (ref "X8") (pin "11") (pinfunction "R1_4_11") (pintype "passive"))
      (node (ref "X8") (pin "12") (pinfunction "GND_12") (pintype "passive"))
      (node (ref "X8") (pin "14") (pinfunction "R2_2_14") (pintype "passive"))
      (node (ref "X8") (pin "6") (pinfunction "R1_7_6") (pintype "passive"))
    )
    (net (code "76") (name "unconnected-(J2-SHLD-Pad5)") (class "Default")
      (node (ref "J2") (pin "5") (pinfunction "SHLD_5") (pintype "passive"))
    )
    (net (code "77") (name "unconnected-(J2-SHLD-Pad6)") (class "Default")
      (node (ref "J2") (pin "6") (pinfunction "SHLD_6") (pintype "passive"))
    )
    (net (code "78") (name "unconnected-(J2-VBUS-Pad1)") (class "Default")
      (node (ref "J2") (pin "1") (pinfunction "VBUS_1") (pintype "power_in"))
    )
    (net (code "79") (name "unconnected-(J3-Pad1)") (class "Default")
      (node (ref "J3") (pin "1") (pinfunction "1_1") (pintype "passive"))
    )
    (net (code "80") (name "unconnected-(J3-Pad3)") (class "Default")
      (node (ref "J3") (pin "3") (pinfunction "3_3") (pintype "passive"))
    )
    (net (code "81") (name "unconnected-(J3-Pad4)") (class "Default")
      (node (ref "J3") (pin "4") (pinfunction "4_4") (pintype "passive"))
    )
    (net (code "82") (name "unconnected-(J3-Pad5)") (class "Default")
      (node (ref "J3") (pin "5") (pinfunction "5_5") (pintype "passive"))
    )
    (net (code "83") (name "unconnected-(J3-Pad9)") (class "Default")
      (node (ref "J3") (pin "9") (pinfunction "9_9") (pintype "passive"))
    )
    (net (code "84") (name "unconnected-(P16-Pad7)") (class "Default")
      (node (ref "P16") (pin "7") (pinfunction "7_7") (pintype "passive"))
    )
    (net (code "85") (name "unconnected-(P16-Pad13)") (class "Default")
      (node (ref "P16") (pin "13") (pinfunction "13_13") (pintype "passive"))
    )
    (net (code "86") (name "unconnected-(P16-Pad14)") (class "Default")
      (node (ref "P16") (pin "14") (pinfunction "14_14") (pintype "passive"))
    )
    (net (code "87") (name "unconnected-(P16-Pad15)") (class "Default")
      (node (ref "P16") (pin "15") (pinfunction "15_15") (pintype "passive"))
    )
    (net (code "88") (name "unconnected-(P17-Pad2)") (class "Default")
      (node (ref "P17") (pin "2") (pinfunction "2_2") (pintype "passive"))
    )
    (net (code "89") (name "unconnected-(P17-Pad3)") (class "Default")
      (node (ref "P17") (pin "3") (pinfunction "3_3") (pintype "passive"))
    )
    (net (code "90") (name "unconnected-(P17-Pad10)") (class "Default")
      (node (ref "P17") (pin "10") (pinfunction "10_10") (pintype "passive"))
    )
    (net (code "91") (name "unconnected-(P17-Pad11)") (class "Default")
      (node (ref "P17") (pin "11") (pinfunction "11_11") (pintype "passive"))
    )
    (net (code "92") (name "unconnected-(P17-Pad12)") (class "Default")
      (node (ref "P17") (pin "12") (pinfunction "12_12") (pintype "passive"))
    )
    (net (code "93") (name "unconnected-(P17-Pad13)") (class "Default")
      (node (ref "P17") (pin "13") (pinfunction "13_13") (pintype "passive"))
    )
    (net (code "94") (name "unconnected-(P17-Pad15)") (class "Default")
      (node (ref "P17") (pin "15") (pinfunction "15_15") (pintype "passive"))
    )
    (net (code "95") (name "unconnected-(X1-R1_5-Pad4)") (class "Default")
      (node (ref "X1") (pin "4") (pinfunction "R1_5_4") (pintype "passive"))
    )
    (net (code "96") (name "unconnected-(X1-R1_6-Pad5)") (class "Default")
      (node (ref "X1") (pin "5") (pinfunction "R1_6_5") (pintype "passive"))
    )
    (net (code "97") (name "unconnected-(X1-R1_7-Pad6)") (class "Default")
      (node (ref "X1") (pin "6") (pinfunction "R1_7_6") (pintype "passive"))
    )
    (net (code "98") (name "unconnected-(X1-R2_5-Pad1)") (class "Default")
      (node (ref "X1") (pin "1") (pinfunction "R2_5_1") (pintype "passive"))
    )
    (net (code "99") (name "unconnected-(X1-R2_6-Pad2)") (class "Default")
      (node (ref "X1") (pin "2") (pinfunction "R2_6_2") (pintype "passive"))
    )
    (net (code "100") (name "unconnected-(X1-R2_7-Pad3)") (class "Default")
      (node (ref "X1") (pin "3") (pinfunction "R2_7_3") (pintype "passive"))
    )
    (net (code "101") (name "unconnected-(X2-R1_5-Pad4)") (class "Default")
      (node (ref "X2") (pin "4") (pinfunction "R1_5_4") (pintype "passive"))
    )
    (net (code "102") (name "unconnected-(X2-R1_6-Pad5)") (class "Default")
      (node (ref "X2") (pin "5") (pinfunction "R1_6_5") (pintype "passive"))
    )
    (net (code "103") (name "unconnected-(X2-R1_7-Pad6)") (class "Default")
      (node (ref "X2") (pin "6") (pinfunction "R1_7_6") (pintype "passive"))
    )
    (net (code "104") (name "unconnected-(X2-R2_5-Pad1)") (class "Default")
      (node (ref "X2") (pin "1") (pinfunction "R2_5_1") (pintype "passive"))
    )
    (net (code "105") (name "unconnected-(X2-R2_6-Pad2)") (class "Default")
      (node (ref "X2") (pin "2") (pinfunction "R2_6_2") (pintype "passive"))
    )
    (net (code "106") (name "unconnected-(X2-R2_7-Pad3)") (class "Default")
      (node (ref "X2") (pin "3") (pinfunction "R2_7_3") (pintype "passive"))
    )
    (net (code "107") (name "unconnected-(X3-R1_5-Pad4)") (class "Default")
      (node (ref "X3") (pin "4") (pinfunction "R1_5_4") (pintype "passive"))
    )
    (net (code "108") (name "unconnected-(X3-R1_6-Pad5)") (class "Default")
      (node (ref "X3") (pin "5") (pinfunction "R1_6_5") (pintype "passive"))
    )
    (net (code "109") (name "unconnected-(X3-R1_7-Pad6)") (class "Default")
      (node (ref "X3") (pin "6") (pinfunction "R1_7_6") (pintype "passive"))
    )
    (net (code "110") (name "unconnected-(X3-R2_5-Pad1)") (class "Default")
      (node (ref "X3") (pin "1") (pinfunction "R2_5_1") (pintype "passive"))
    )
    (net (code "111") (name "unconnected-(X3-R2_6-Pad2)") (class "Default")
      (node (ref "X3") (pin "2") (pinfunction "R2_6_2") (pintype "passive"))
    )
    (net (code "112") (name "unconnected-(X3-R2_7-Pad3)") (class "Default")
      (node (ref "X3") (pin "3") (pinfunction "R2_7_3") (pintype "passive"))
    )
    (net (code "113") (name "unconnected-(X4-R1_5-Pad4)") (class "Default")
      (node (ref "X4") (pin "4") (pinfunction "R1_5_4") (pintype "passive"))
    )
    (net (code "114") (name "unconnected-(X4-R1_6-Pad5)") (class "Default")
      (node (ref "X4") (pin "5") (pinfunction "R1_6_5") (pintype "passive"))
    )
    (net (code "115") (name "unconnected-(X4-R1_7-Pad6)") (class "Default")
      (node (ref "X4") (pin "6") (pinfunction "R1_7_6") (pintype "passive"))
    )
    (net (code "116") (name "unconnected-(X4-R2_5-Pad1)") (class "Default")
      (node (ref "X4") (pin "1") (pinfunction "R2_5_1") (pintype "passive"))
    )
    (net (code "117") (name "unconnected-(X4-R2_6-Pad2)") (class "Default")
      (node (ref "X4") (pin "2") (pinfunction "R2_6_2") (pintype "passive"))
    )
    (net (code "118") (name "unconnected-(X4-R2_7-Pad3)") (class "Default")
      (node (ref "X4") (pin "3") (pinfunction "R2_7_3") (pintype "passive"))
    )
    (net (code "119") (name "unconnected-(X5-R1_5-Pad4)") (class "Default")
      (node (ref "X5") (pin "4") (pinfunction "R1_5_4") (pintype "passive"))
    )
    (net (code "120") (name "unconnected-(X5-R1_6-Pad5)") (class "Default")
      (node (ref "X5") (pin "5") (pinfunction "R1_6_5") (pintype "passive"))
    )
    (net (code "121") (name "unconnected-(X5-R1_7-Pad6)") (class "Default")
      (node (ref "X5") (pin "6") (pinfunction "R1_7_6") (pintype "passive"))
    )
    (net (code "122") (name "unconnected-(X5-R2_5-Pad1)") (class "Default")
      (node (ref "X5") (pin "1") (pinfunction "R2_5_1") (pintype "passive"))
    )
    (net (code "123") (name "unconnected-(X5-R2_6-Pad2)") (class "Default")
      (node (ref "X5") (pin "2") (pinfunction "R2_6_2") (pintype "passive"))
    )
    (net (code "124") (name "unconnected-(X5-R2_7-Pad3)") (class "Default")
      (node (ref "X5") (pin "3") (pinfunction "R2_7_3") (pintype "passive"))
    )
    (net (code "125") (name "unconnected-(X6-R1_5-Pad4)") (class "Default")
      (node (ref "X6") (pin "4") (pinfunction "R1_5_4") (pintype "passive"))
    )
    (net (code "126") (name "unconnected-(X6-R1_6-Pad5)") (class "Default")
      (node (ref "X6") (pin "5") (pinfunction "R1_6_5") (pintype "passive"))
    )
    (net (code "127") (name "unconnected-(X6-R1_7-Pad6)") (class "Default")
      (node (ref "X6") (pin "6") (pinfunction "R1_7_6") (pintype "passive"))
    )
    (net (code "128") (name "unconnected-(X6-R2_5-Pad1)") (class "Default")
      (node (ref "X6") (pin "1") (pinfunction "R2_5_1") (pintype "passive"))
    )
    (net (code "129") (name "unconnected-(X6-R2_6-Pad2)") (class "Default")
      (node (ref "X6") (pin "2") (pinfunction "R2_6_2") (pintype "passive"))
    )
    (net (code "130") (name "unconnected-(X6-R2_7-Pad3)") (class "Default")
      (node (ref "X6") (pin "3") (pinfunction "R2_7_3") (pintype "passive"))
    )
    (net (code "131") (name "unconnected-(X7-R1_5-Pad4)") (class "Default")
      (node (ref "X7") (pin "4") (pinfunction "R1_5_4") (pintype "passive"))
    )
    (net (code "132") (name "unconnected-(X7-R1_6-Pad5)") (class "Default")
      (node (ref "X7") (pin "5") (pinfunction "R1_6_5") (pintype "passive"))
    )
    (net (code "133") (name "unconnected-(X7-R1_7-Pad6)") (class "Default")
      (node (ref "X7") (pin "6") (pinfunction "R1_7_6") (pintype "passive"))
    )
    (net (code "134") (name "unconnected-(X7-R2_5-Pad1)") (class "Default")
      (node (ref "X7") (pin "1") (pinfunction "R2_5_1") (pintype "passive"))
    )
    (net (code "135") (name "unconnected-(X7-R2_6-Pad2)") (class "Default")
      (node (ref "X7") (pin "2") (pinfunction "R2_6_2") (pintype "passive"))
    )
    (net (code "136") (name "unconnected-(X7-R2_7-Pad3)") (class "Default")
      (node (ref "X7") (pin "3") (pinfunction "R2_7_3") (pintype "passive"))
    )
    (net (code "137") (name "unconnected-(X8-R2_5-Pad1)") (class "Default")
      (node (ref "X8") (pin "1") (pinfunction "R2_5_1") (pintype "passive"))
    )
    (net (code "138") (name "unconnected-(X8-R2_6-Pad2)") (class "Default")
      (node (ref "X8") (pin "2") (pinfunction "R2_6_2") (pintype "passive"))
    )
    (net (code "139") (name "unconnected-(X8-R2_7-Pad3)") (class "Default")
      (node (ref "X8") (pin "3") (pinfunction "R2_7_3") (pintype "passive"))
    )
    (net (code "140") (name "unconnected-(X9-+V-Pad3)") (class "Default")
      (node (ref "X9") (pin "3") (pinfunction "+V_3") (pintype "passive"))
    )
    (net (code "141") (name "unconnected-(X9--V-Pad4)") (class "Default")
      (node (ref "X9") (pin "4") (pinfunction "-V_4") (pintype "passive"))
    )
  )
)
